# breakout-ws2812.net
KiCad netlist of a schematic drawn in EAGLE
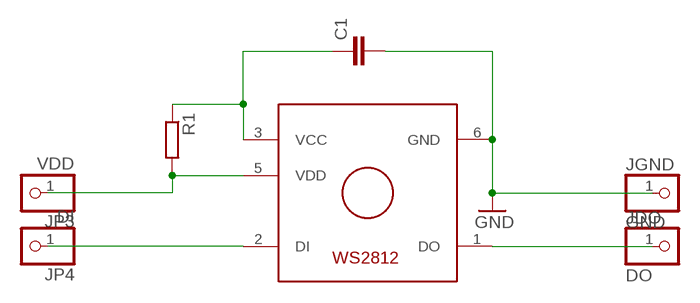
[diagram p0: schematic, sheet 1]

(export (version "E")
  (design (tool "Eeschema 10.0.6"))
  (components
    (comp (ref "C1")
      (value "C-EUC1206")
      (footprint "eagle-import:C1206")
      (libsource (lib "eagle-import") (part "C-EUC1206"))
    )
    (comp (ref "JDO")
      (value "DO")
      (footprint "eagle-import:1X01")
      (libsource (lib "eagle-import") (part "PINHD-1X1"))
    )
    (comp (ref "JGND")
      (value "GND")
      (footprint "eagle-import:1X01")
      (libsource (lib "eagle-import") (part "PINHD-1X1"))
    )
    (comp (ref "JP3")
      (value "VDD")
      (footprint "eagle-import:1X01")
      (libsource (lib "eagle-import") (part "PINHD-1X1"))
    )
    (comp (ref "JP4")
      (value "DI")
      (footprint "eagle-import:1X01")
      (libsource (lib "eagle-import") (part "PINHD-1X1"))
    )
    (comp (ref "R1")
      (value "R-EU_R1206")
      (footprint "eagle-import:R1206")
      (libsource (lib "eagle-import") (part "R-EU_R1206"))
    )
    (comp (ref "U$1")
      (value "WS2812")
      (footprint "eagle-import:WS2812")
      (libsource (lib "eagle-import") (part "WS2812"))
    )
  )
  (nets
    (net (code "1") (name "GND") (class "Default")
      (node (ref "C1") (pin "2") (pinfunction "2_2") (pintype "passive"))
      (node (ref "JGND") (pin "1") (pinfunction "1_1") (pintype "passive"))
      (node (ref "U$1") (pin "6") (pinfunction "GND_6") (pintype "power_in"))
    )
    (net (code "2") (name "Net-(U$1-DI)") (class "Default")
      (node (ref "JP4") (pin "1") (pinfunction "1_1") (pintype "passive"))
      (node (ref "U$1") (pin "2") (pinfunction "DI_2") (pintype "input"))
    )
    (net (code "3") (name "Net-(U$1-DO)") (class "Default")
      (node (ref "JDO") (pin "1") (pinfunction "1_1") (pintype "passive"))
      (node (ref "U$1") (pin "1") (pinfunction "DO_1") (pintype "output"))
    )
    (net (code "4") (name "Net-(U$1-VCC)") (class "Default")
      (node (ref "C1") (pin "1") (pinfunction "1_1") (pintype "passive"))
      (node (ref "R1") (pin "1") (pinfunction "1_1") (pintype "passive"))
      (node (ref "U$1") (pin "3") (pinfunction "VCC_3") (pintype "power_in"))
    )
    (net (code "5") (name "Net-(U$1-VDD)") (class "Default")
      (node (ref "JP3") (pin "1") (pinfunction "1_1") (pintype "passive"))
      (node (ref "R1") (pin "2") (pinfunction "2_2") (pintype "passive"))
      (node (ref "U$1") (pin "5") (pinfunction "VDD_5") (pintype "power_in"))
    )
  )
)
